# myDuino_v1_0.net
KiCad netlist of a schematic drawn in EAGLE
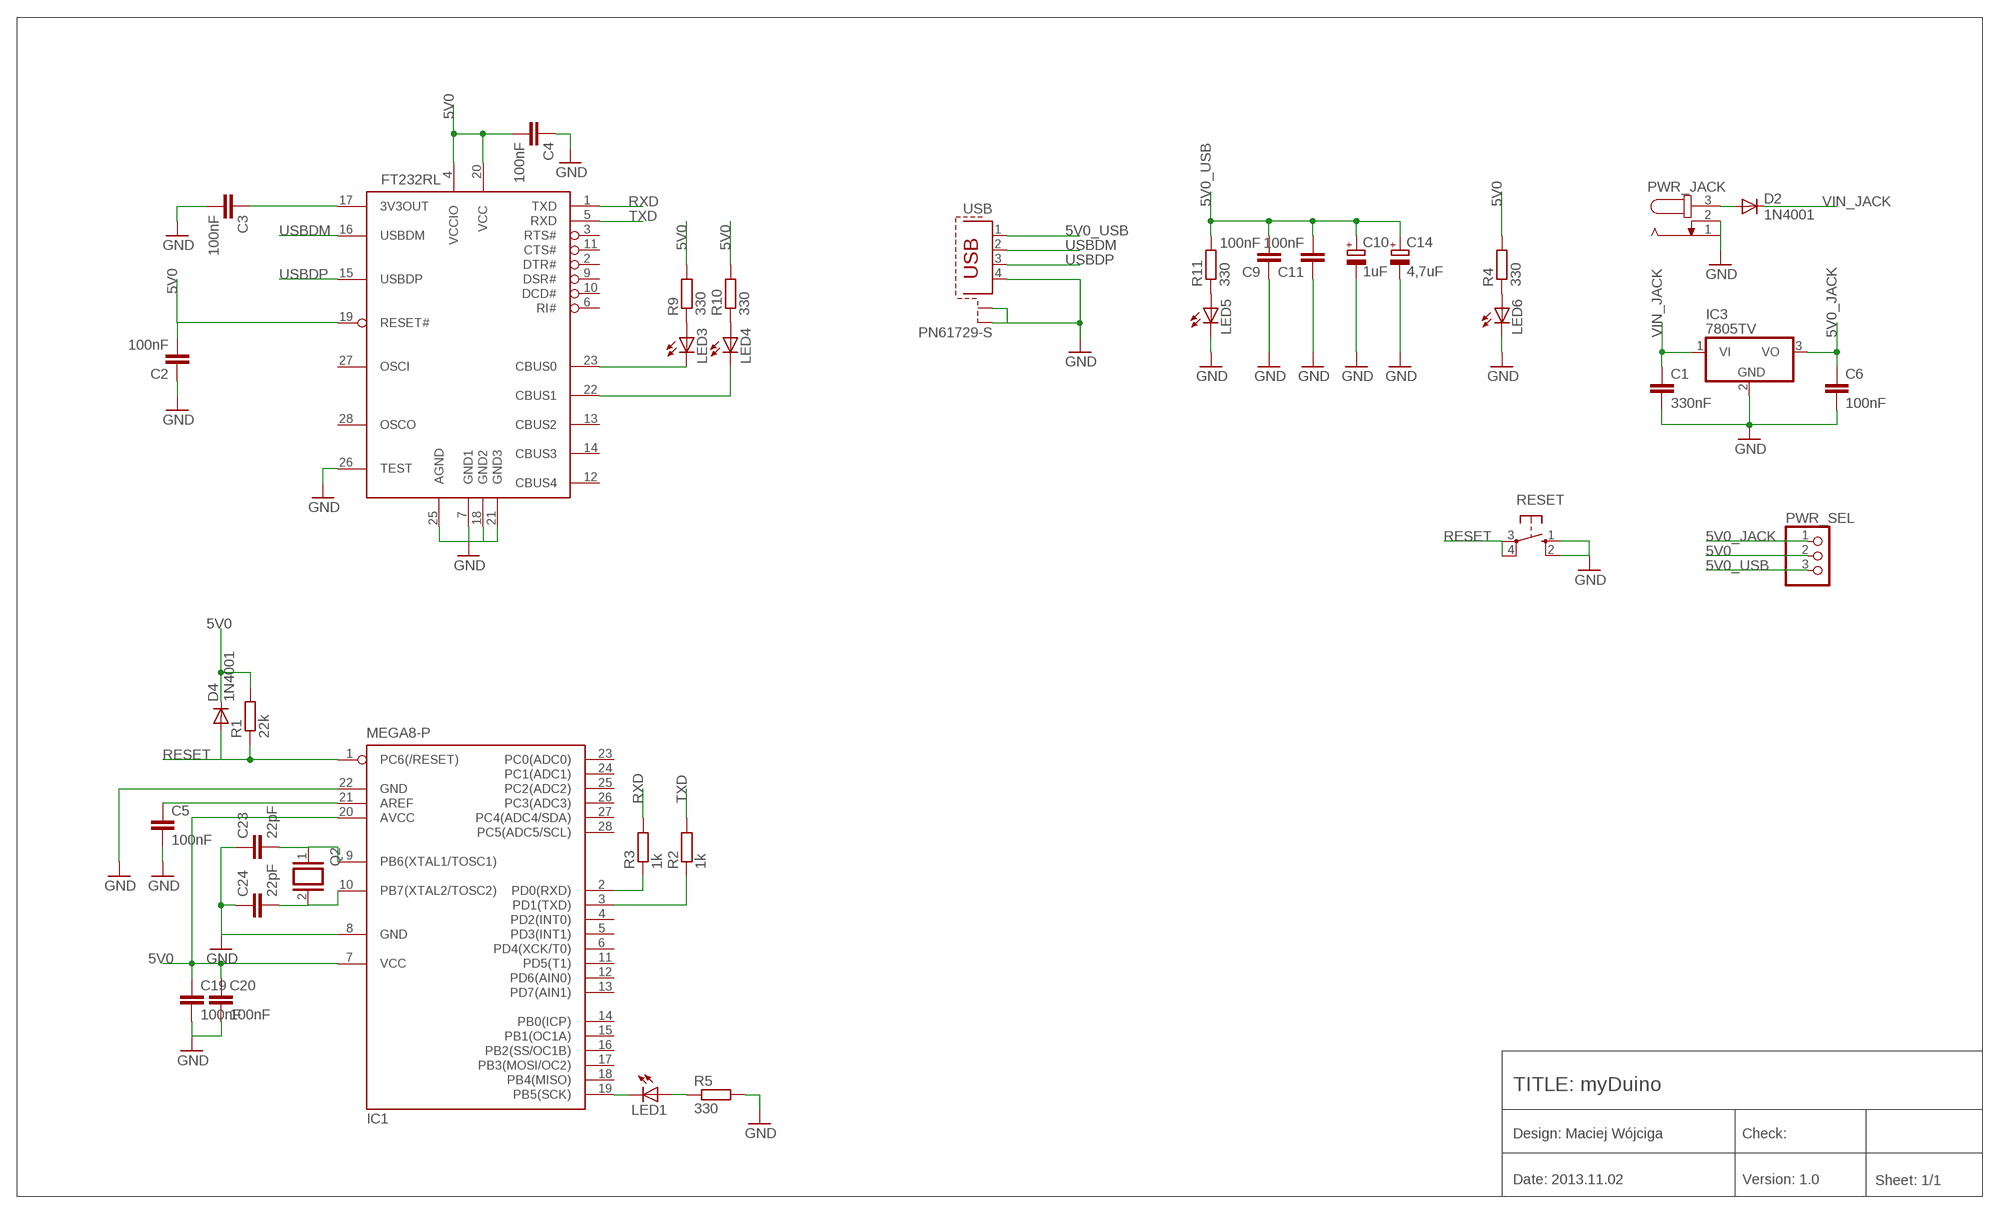
[diagram p0: schematic, sheet 1]

(export (version "E")
  (design (tool "Eeschema 10.0.6"))
  (components
    (comp (ref "C1")
      (value "330nF")
      (footprint "eagle-import:C025-025X050")
      (libsource (lib "eagle-import") (part "C-EU025-025X050"))
    )
    (comp (ref "C2")
      (value "100nF")
      (footprint "eagle-import:C025-025X050")
      (libsource (lib "eagle-import") (part "C-EU025-025X050"))
    )
    (comp (ref "C3")
      (value "100nF")
      (footprint "eagle-import:C025-025X050")
      (libsource (lib "eagle-import") (part "C-EU025-025X050"))
    )
    (comp (ref "C4")
      (value "100nF")
      (footprint "eagle-import:C025-025X050")
      (libsource (lib "eagle-import") (part "C-EU025-025X050"))
    )
    (comp (ref "C5")
      (value "100nF")
      (footprint "eagle-import:C025-025X050")
      (libsource (lib "eagle-import") (part "C-EU025-025X050"))
    )
    (comp (ref "C6")
      (value "100nF")
      (footprint "eagle-import:C025-025X050")
      (libsource (lib "eagle-import") (part "C-EU025-025X050"))
    )
    (comp (ref "C9")
      (value "100nF")
      (footprint "eagle-import:C025-025X050")
      (libsource (lib "eagle-import") (part "C-EU025-025X050"))
    )
    (comp (ref "C10")
      (value "1uF")
      (footprint "eagle-import:E2,5-5")
      (libsource (lib "eagle-import") (part "CPOL-EUE2.5-5"))
    )
    (comp (ref "C11")
      (value "100nF")
      (footprint "eagle-import:C025-025X050")
      (libsource (lib "eagle-import") (part "C-EU025-025X050"))
    )
    (comp (ref "C14")
      (value "4,7uF")
      (footprint "eagle-import:E2,5-5")
      (libsource (lib "eagle-import") (part "CPOL-EUE2.5-5"))
    )
    (comp (ref "C19")
      (value "100nF")
      (footprint "eagle-import:C025-025X050")
      (libsource (lib "eagle-import") (part "C-EU025-025X050"))
    )
    (comp (ref "C20")
      (value "100nF")
      (footprint "eagle-import:C025-025X050")
      (libsource (lib "eagle-import") (part "C-EU025-025X050"))
    )
    (comp (ref "C23")
      (value "22pF")
      (footprint "eagle-import:C025-025X050")
      (libsource (lib "eagle-import") (part "C-EU025-025X050"))
    )
    (comp (ref "C24")
      (value "22pF")
      (footprint "eagle-import:C025-025X050")
      (libsource (lib "eagle-import") (part "C-EU025-025X050"))
    )
    (comp (ref "D2")
      (value "1N4001")
      (footprint "eagle-import:DO41-10")
      (libsource (lib "eagle-import") (part "1N4004"))
    )
    (comp (ref "D4")
      (value "1N4001")
      (footprint "eagle-import:DO41-10")
      (libsource (lib "eagle-import") (part "1N4004"))
    )
    (comp (ref "FT232RL")
      (value "FT232RL")
      (footprint "eagle-import:SSOP28DB")
      (libsource (lib "eagle-import") (part "FT232RL"))
    )
    (comp (ref "IC1")
      (value "MEGA8-P")
      (footprint "eagle-import:DIL28-3")
      (libsource (lib "eagle-import") (part "MEGA8-P"))
    )
    (comp (ref "IC3")
      (value "7805TV")
      (footprint "eagle-import:TO220V")
      (libsource (lib "eagle-import") (part "78TV05"))
    )
    (comp (ref "LED1")
      (value "LED3MM")
      (footprint "eagle-import:LED3MM")
      (libsource (lib "eagle-import") (part "LED3MM"))
    )
    (comp (ref "LED3")
      (value "LED3MM")
      (footprint "eagle-import:LED3MM")
      (libsource (lib "eagle-import") (part "LED3MM"))
    )
    (comp (ref "LED4")
      (value "LED3MM")
      (footprint "eagle-import:LED3MM")
      (libsource (lib "eagle-import") (part "LED3MM"))
    )
    (comp (ref "LED5")
      (value "LED3MM")
      (footprint "eagle-import:LED3MM")
      (libsource (lib "eagle-import") (part "LED3MM"))
    )
    (comp (ref "LED6")
      (value "LED3MM")
      (footprint "eagle-import:LED3MM")
      (libsource (lib "eagle-import") (part "LED3MM"))
    )
    (comp (ref "PWR_JACK")
      (value "JACK-PLUG0")
      (footprint "eagle-import:SPC4077")
      (libsource (lib "eagle-import") (part "JACK-PLUG0"))
    )
    (comp (ref "PWR_SEL")
      (value "PINHD-1X3")
      (footprint "eagle-import:1X03")
      (libsource (lib "eagle-import") (part "PINHD-1X3"))
    )
    (comp (ref "Q2")
      (value "XTAL/S")
      (footprint "eagle-import:QS")
      (libsource (lib "eagle-import") (part "XTAL/S"))
    )
    (comp (ref "R1")
      (value "22k")
      (footprint "eagle-import:0207_10")
      (libsource (lib "eagle-import") (part "R-EU_0207/10"))
    )
    (comp (ref "R2")
      (value "1k")
      (footprint "eagle-import:0207_10")
      (libsource (lib "eagle-import") (part "R-EU_0207/10"))
    )
    (comp (ref "R3")
      (value "1k")
      (footprint "eagle-import:0207_10")
      (libsource (lib "eagle-import") (part "R-EU_0207/10"))
    )
    (comp (ref "R4")
      (value "330")
      (footprint "eagle-import:0207_10")
      (libsource (lib "eagle-import") (part "R-EU_0207/10"))
    )
    (comp (ref "R5")
      (value "330")
      (footprint "eagle-import:0207_10")
      (libsource (lib "eagle-import") (part "R-EU_0207/10"))
    )
    (comp (ref "R9")
      (value "330")
      (footprint "eagle-import:0207_10")
      (libsource (lib "eagle-import") (part "R-EU_0207/10"))
    )
    (comp (ref "R10")
      (value "330")
      (footprint "eagle-import:0207_10")
      (libsource (lib "eagle-import") (part "R-EU_0207/10"))
    )
    (comp (ref "R11")
      (value "330")
      (footprint "eagle-import:0207_10")
      (libsource (lib "eagle-import") (part "R-EU_0207/10"))
    )
    (comp (ref "RESET")
      (value "10-XX")
      (footprint "eagle-import:B3F-10XX")
      (fields (field (name "MPN") "B3F-1000"))
      (libsource (lib "eagle-import") (part "10-XX"))
    )
    (comp (ref "USB")
      (value "PN61729-S")
      (footprint "eagle-import:PN61729-S")
      (fields (field (name "OC_FARNELL") "unknown") (field (name "OC_NEWARK") "unknown"))
      (libsource (lib "eagle-import") (part "PN61729-S"))
    )
  )
  (nets
    (net (code "1") (name "/5V0") (class "Default")
      (node (ref "C19") (pin "1") (pinfunction "1_1") (pintype "passive"))
      (node (ref "C2") (pin "2") (pinfunction "2_2") (pintype "passive"))
      (node (ref "C20") (pin "1") (pinfunction "1_1") (pintype "passive"))
      (node (ref "C4") (pin "2") (pinfunction "2_2") (pintype "passive"))
      (node (ref "D4") (pin "C") (pinfunction "C_C") (pintype "passive"))
      (node (ref "FT232RL") (pin "19") (pinfunction "RESET#_19") (pintype "input"))
      (node (ref "FT232RL") (pin "20") (pinfunction "VCC_20") (pintype "power_in"))
      (node (ref "FT232RL") (pin "4") (pinfunction "VCCIO_4") (pintype "power_in"))
      (node (ref "IC1") (pin "20") (pinfunction "AVCC_20") (pintype "power_in"))
      (node (ref "IC1") (pin "7") (pinfunction "VCC_7") (pintype "power_in"))
      (node (ref "PWR_SEL") (pin "2") (pinfunction "2_2") (pintype "passive"))
      (node (ref "R1") (pin "2") (pinfunction "2_2") (pintype "passive"))
      (node (ref "R10") (pin "2") (pinfunction "2_2") (pintype "passive"))
      (node (ref "R4") (pin "2") (pinfunction "2_2") (pintype "passive"))
      (node (ref "R9") (pin "2") (pinfunction "2_2") (pintype "passive"))
    )
    (net (code "2") (name "/5V0_JACK") (class "Default")
      (node (ref "C6") (pin "1") (pinfunction "1_1") (pintype "passive"))
      (node (ref "IC3") (pin "3") (pinfunction "VO_3") (pintype "passive"))
      (node (ref "PWR_SEL") (pin "1") (pinfunction "1_1") (pintype "passive"))
    )
    (net (code "3") (name "/5V0_USB") (class "Default")
      (node (ref "C10") (pin "+") (pinfunction "+_+") (pintype "passive"))
      (node (ref "C11") (pin "2") (pinfunction "2_2") (pintype "passive"))
      (node (ref "C14") (pin "+") (pinfunction "+_+") (pintype "passive"))
      (node (ref "C9") (pin "2") (pinfunction "2_2") (pintype "passive"))
      (node (ref "PWR_SEL") (pin "3") (pinfunction "3_3") (pintype "passive"))
      (node (ref "R11") (pin "2") (pinfunction "2_2") (pintype "passive"))
      (node (ref "USB") (pin "1") (pinfunction "1_1") (pintype "passive"))
    )
    (net (code "4") (name "/RESET") (class "Default")
      (node (ref "D4") (pin "A") (pinfunction "A_A") (pintype "passive"))
      (node (ref "IC1") (pin "1") (pinfunction "PC6(/RESET)_1") (pintype "bidirectional"))
      (node (ref "R1") (pin "1") (pinfunction "1_1") (pintype "passive"))
      (node (ref "RESET") (pin "3") (pinfunction "P_3") (pintype "passive"))
      (node (ref "RESET") (pin "4") (pinfunction "P1_4") (pintype "passive"))
    )
    (net (code "5") (name "/RXD") (class "Default")
      (node (ref "FT232RL") (pin "1") (pinfunction "TXD_1") (pintype "output"))
      (node (ref "R3") (pin "2") (pinfunction "2_2") (pintype "passive"))
    )
    (net (code "6") (name "/TXD") (class "Default")
      (node (ref "FT232RL") (pin "5") (pinfunction "RXD_5") (pintype "input"))
      (node (ref "R2") (pin "2") (pinfunction "2_2") (pintype "passive"))
    )
    (net (code "7") (name "/USBDM") (class "Default")
      (node (ref "FT232RL") (pin "16") (pinfunction "USBDM_16") (pintype "bidirectional"))
      (node (ref "USB") (pin "2") (pinfunction "2_2") (pintype "passive"))
    )
    (net (code "8") (name "/USBDP") (class "Default")
      (node (ref "FT232RL") (pin "15") (pinfunction "USBDP_15") (pintype "bidirectional"))
      (node (ref "USB") (pin "3") (pinfunction "3_3") (pintype "passive"))
    )
    (net (code "9") (name "/VIN_JACK") (class "Default")
      (node (ref "C1") (pin "1") (pinfunction "1_1") (pintype "passive"))
      (node (ref "D2") (pin "C") (pinfunction "C_C") (pintype "passive"))
      (node (ref "IC3") (pin "1") (pinfunction "VI_1") (pintype "input"))
    )
    (net (code "10") (name "GND") (class "Default")
      (node (ref "C1") (pin "2") (pinfunction "2_2") (pintype "passive"))
      (node (ref "C10") (pin "-") (pinfunction "-_-") (pintype "passive"))
      (node (ref "C11") (pin "1") (pinfunction "1_1") (pintype "passive"))
      (node (ref "C14") (pin "-") (pinfunction "-_-") (pintype "passive"))
      (node (ref "C19") (pin "2") (pinfunction "2_2") (pintype "passive"))
      (node (ref "C2") (pin "1") (pinfunction "1_1") (pintype "passive"))
      (node (ref "C20") (pin "2") (pinfunction "2_2") (pintype "passive"))
      (node (ref "C23") (pin "1") (pinfunction "1_1") (pintype "passive"))
      (node (ref "C24") (pin "1") (pinfunction "1_1") (pintype "passive"))
      (node (ref "C3") (pin "2") (pinfunction "2_2") (pintype "passive"))
      (node (ref "C4") (pin "1") (pinfunction "1_1") (pintype "passive"))
      (node (ref "C5") (pin "2") (pinfunction "2_2") (pintype "passive"))
      (node (ref "C6") (pin "2") (pinfunction "2_2") (pintype "passive"))
      (node (ref "C9") (pin "1") (pinfunction "1_1") (pintype "passive"))
      (node (ref "FT232RL") (pin "18") (pinfunction "GND2_18") (pintype "power_in"))
      (node (ref "FT232RL") (pin "21") (pinfunction "GND3_21") (pintype "power_in"))
      (node (ref "FT232RL") (pin "25") (pinfunction "AGND_25") (pintype "power_in"))
      (node (ref "FT232RL") (pin "26") (pinfunction "TEST_26") (pintype "input"))
      (node (ref "FT232RL") (pin "7") (pinfunction "GND1_7") (pintype "power_in"))
      (node (ref "IC1") (pin "22") (pinfunction "GND_22") (pintype "power_in"))
      (node (ref "IC1") (pin "8") (pinfunction "GND_8") (pintype "power_in"))
      (node (ref "IC3") (pin "2") (pinfunction "GND_2") (pintype "passive"))
      (node (ref "LED5") (pin "K") (pinfunction "C_K") (pintype "passive"))
      (node (ref "LED6") (pin "K") (pinfunction "C_K") (pintype "passive"))
      (node (ref "PWR_JACK") (pin "1") (pinfunction "1_1") (pintype "passive"))
      (node (ref "PWR_JACK") (pin "2") (pinfunction "2_2") (pintype "passive"))
      (node (ref "R5") (pin "2") (pinfunction "2_2") (pintype "passive"))
      (node (ref "RESET") (pin "1") (pinfunction "S_1") (pintype "passive"))
      (node (ref "RESET") (pin "2") (pinfunction "S1_2") (pintype "passive"))
      (node (ref "USB") (pin "4") (pinfunction "4_4") (pintype "passive"))
      (node (ref "USB") (pin "S1") (pinfunction "S1_S1") (pintype "passive"))
      (node (ref "USB") (pin "S2") (pinfunction "S2_S2") (pintype "passive"))
    )
    (net (code "11") (name "Net-(D2-PadA)") (class "Default")
      (node (ref "D2") (pin "A") (pinfunction "A_A") (pintype "passive"))
      (node (ref "PWR_JACK") (pin "3") (pinfunction "3_3") (pintype "passive"))
    )
    (net (code "12") (name "Net-(FT232RL-3V3OUT)") (class "Default")
      (node (ref "C3") (pin "1") (pinfunction "1_1") (pintype "passive"))
      (node (ref "FT232RL") (pin "17") (pinfunction "3V3OUT_17") (pintype "output"))
    )
    (net (code "13") (name "Net-(FT232RL-CBUS0)") (class "Default")
      (node (ref "FT232RL") (pin "23") (pinfunction "CBUS0_23") (pintype "bidirectional"))
      (node (ref "LED3") (pin "K") (pinfunction "C_K") (pintype "passive"))
    )
    (net (code "14") (name "Net-(FT232RL-CBUS1)") (class "Default")
      (node (ref "FT232RL") (pin "22") (pinfunction "CBUS1_22") (pintype "bidirectional"))
      (node (ref "LED4") (pin "K") (pinfunction "C_K") (pintype "passive"))
    )
    (net (code "15") (name "Net-(IC1-AREF)") (class "Default")
      (node (ref "C5") (pin "1") (pinfunction "1_1") (pintype "passive"))
      (node (ref "IC1") (pin "21") (pinfunction "AREF_21") (pintype "passive"))
    )
    (net (code "16") (name "Net-(IC1-PB5(SCK))") (class "Default")
      (node (ref "IC1") (pin "19") (pinfunction "PB5(SCK)_19") (pintype "bidirectional"))
      (node (ref "LED1") (pin "K") (pinfunction "C_K") (pintype "passive"))
    )
    (net (code "17") (name "Net-(IC1-PB6(XTAL1{slash}TOSC1))") (class "Default")
      (node (ref "C23") (pin "2") (pinfunction "2_2") (pintype "passive"))
      (node (ref "IC1") (pin "9") (pinfunction "PB6(XTAL1/TOSC1)_9") (pintype "bidirectional"))
      (node (ref "Q2") (pin "1") (pinfunction "1_1") (pintype "passive"))
    )
    (net (code "18") (name "Net-(IC1-PB7(XTAL2{slash}TOSC2))") (class "Default")
      (node (ref "C24") (pin "2") (pinfunction "2_2") (pintype "passive"))
      (node (ref "IC1") (pin "10") (pinfunction "PB7(XTAL2/TOSC2)_10") (pintype "bidirectional"))
      (node (ref "Q2") (pin "2") (pinfunction "2_2") (pintype "passive"))
    )
    (net (code "19") (name "Net-(IC1-PD0(RXD))") (class "Default")
      (node (ref "IC1") (pin "2") (pinfunction "PD0(RXD)_2") (pintype "bidirectional"))
      (node (ref "R3") (pin "1") (pinfunction "1_1") (pintype "passive"))
    )
    (net (code "20") (name "Net-(IC1-PD1(TXD))") (class "Default")
      (node (ref "IC1") (pin "3") (pinfunction "PD1(TXD)_3") (pintype "bidirectional"))
      (node (ref "R2") (pin "1") (pinfunction "1_1") (pintype "passive"))
    )
    (net (code "21") (name "Net-(LED1-PadA)") (class "Default")
      (node (ref "LED1") (pin "A") (pinfunction "A_A") (pintype "passive"))
      (node (ref "R5") (pin "1") (pinfunction "1_1") (pintype "passive"))
    )
    (net (code "22") (name "Net-(LED3-PadA)") (class "Default")
      (node (ref "LED3") (pin "A") (pinfunction "A_A") (pintype "passive"))
      (node (ref "R9") (pin "1") (pinfunction "1_1") (pintype "passive"))
    )
    (net (code "23") (name "Net-(LED4-PadA)") (class "Default")
      (node (ref "LED4") (pin "A") (pinfunction "A_A") (pintype "passive"))
      (node (ref "R10") (pin "1") (pinfunction "1_1") (pintype "passive"))
    )
    (net (code "24") (name "Net-(LED5-PadA)") (class "Default")
      (node (ref "LED5") (pin "A") (pinfunction "A_A") (pintype "passive"))
      (node (ref "R11") (pin "1") (pinfunction "1_1") (pintype "passive"))
    )
    (net (code "25") (name "Net-(LED6-PadA)") (class "Default")
      (node (ref "LED6") (pin "A") (pinfunction "A_A") (pintype "passive"))
      (node (ref "R4") (pin "1") (pinfunction "1_1") (pintype "passive"))
    )
    (net (code "26") (name "unconnected-(FT232RL-CBUS2-Pad13)") (class "Default")
      (node (ref "FT232RL") (pin "13") (pinfunction "CBUS2_13") (pintype "bidirectional"))
    )
    (net (code "27") (name "unconnected-(FT232RL-CBUS3-Pad14)") (class "Default")
      (node (ref "FT232RL") (pin "14") (pinfunction "CBUS3_14") (pintype "bidirectional"))
    )
    (net (code "28") (name "unconnected-(FT232RL-CBUS4-Pad12)") (class "Default")
      (node (ref "FT232RL") (pin "12") (pinfunction "CBUS4_12") (pintype "bidirectional"))
    )
    (net (code "29") (name "unconnected-(FT232RL-CTS#-Pad11)") (class "Default")
      (node (ref "FT232RL") (pin "11") (pinfunction "CTS#_11") (pintype "input"))
    )
    (net (code "30") (name "unconnected-(FT232RL-DCD#-Pad10)") (class "Default")
      (node (ref "FT232RL") (pin "10") (pinfunction "DCD#_10") (pintype "input"))
    )
    (net (code "31") (name "unconnected-(FT232RL-DSR#-Pad9)") (class "Default")
      (node (ref "FT232RL") (pin "9") (pinfunction "DSR#_9") (pintype "input"))
    )
    (net (code "32") (name "unconnected-(FT232RL-DTR#-Pad2)") (class "Default")
      (node (ref "FT232RL") (pin "2") (pinfunction "DTR#_2") (pintype "output"))
    )
    (net (code "33") (name "unconnected-(FT232RL-OSCI-Pad27)") (class "Default")
      (node (ref "FT232RL") (pin "27") (pinfunction "OSCI_27") (pintype "input"))
    )
    (net (code "34") (name "unconnected-(FT232RL-OSCO-Pad28)") (class "Default")
      (node (ref "FT232RL") (pin "28") (pinfunction "OSCO_28") (pintype "output"))
    )
    (net (code "35") (name "unconnected-(FT232RL-RI#-Pad6)") (class "Default")
      (node (ref "FT232RL") (pin "6") (pinfunction "RI#_6") (pintype "input"))
    )
    (net (code "36") (name "unconnected-(FT232RL-RTS#-Pad3)") (class "Default")
      (node (ref "FT232RL") (pin "3") (pinfunction "RTS#_3") (pintype "output"))
    )
    (net (code "37") (name "unconnected-(IC1-PB0(ICP)-Pad14)") (class "Default")
      (node (ref "IC1") (pin "14") (pinfunction "PB0(ICP)_14") (pintype "bidirectional"))
    )
    (net (code "38") (name "unconnected-(IC1-PB1(OC1A)-Pad15)") (class "Default")
      (node (ref "IC1") (pin "15") (pinfunction "PB1(OC1A)_15") (pintype "bidirectional"))
    )
    (net (code "39") (name "unconnected-(IC1-PB2(SS{slash}OC1B)-Pad16)") (class "Default")
      (node (ref "IC1") (pin "16") (pinfunction "PB2(SS/OC1B)_16") (pintype "bidirectional"))
    )
    (net (code "40") (name "unconnected-(IC1-PB3(MOSI{slash}OC2)-Pad17)") (class "Default")
      (node (ref "IC1") (pin "17") (pinfunction "PB3(MOSI/OC2)_17") (pintype "bidirectional"))
    )
    (net (code "41") (name "unconnected-(IC1-PB4(MISO)-Pad18)") (class "Default")
      (node (ref "IC1") (pin "18") (pinfunction "PB4(MISO)_18") (pintype "bidirectional"))
    )
    (net (code "42") (name "unconnected-(IC1-PC0(ADC0)-Pad23)") (class "Default")
      (node (ref "IC1") (pin "23") (pinfunction "PC0(ADC0)_23") (pintype "bidirectional"))
    )
    (net (code "43") (name "unconnected-(IC1-PC1(ADC1)-Pad24)") (class "Default")
      (node (ref "IC1") (pin "24") (pinfunction "PC1(ADC1)_24") (pintype "bidirectional"))
    )
    (net (code "44") (name "unconnected-(IC1-PC2(ADC2)-Pad25)") (class "Default")
      (node (ref "IC1") (pin "25") (pinfunction "PC2(ADC2)_25") (pintype "bidirectional"))
    )
    (net (code "45") (name "unconnected-(IC1-PC3(ADC3)-Pad26)") (class "Default")
      (node (ref "IC1") (pin "26") (pinfunction "PC3(ADC3)_26") (pintype "bidirectional"))
    )
    (net (code "46") (name "unconnected-(IC1-PC4(ADC4{slash}SDA)-Pad27)") (class "Default")
      (node (ref "IC1") (pin "27") (pinfunction "PC4(ADC4/SDA)_27") (pintype "bidirectional"))
    )
    (net (code "47") (name "unconnected-(IC1-PC5(ADC5{slash}SCL)-Pad28)") (class "Default")
      (node (ref "IC1") (pin "28") (pinfunction "PC5(ADC5/SCL)_28") (pintype "bidirectional"))
    )
    (net (code "48") (name "unconnected-(IC1-PD2(INT0)-Pad4)") (class "Default")
      (node (ref "IC1") (pin "4") (pinfunction "PD2(INT0)_4") (pintype "bidirectional"))
    )
    (net (code "49") (name "unconnected-(IC1-PD3(INT1)-Pad5)") (class "Default")
      (node (ref "IC1") (pin "5") (pinfunction "PD3(INT1)_5") (pintype "bidirectional"))
    )
    (net (code "50") (name "unconnected-(IC1-PD4(XCK{slash}T0)-Pad6)") (class "Default")
      (node (ref "IC1") (pin "6") (pinfunction "PD4(XCK/T0)_6") (pintype "bidirectional"))
    )
    (net (code "51") (name "unconnected-(IC1-PD5(T1)-Pad11)") (class "Default")
      (node (ref "IC1") (pin "11") (pinfunction "PD5(T1)_11") (pintype "bidirectional"))
    )
    (net (code "52") (name "unconnected-(IC1-PD6(AIN0)-Pad12)") (class "Default")
      (node (ref "IC1") (pin "12") (pinfunction "PD6(AIN0)_12") (pintype "bidirectional"))
    )
    (net (code "53") (name "unconnected-(IC1-PD7(AIN1)-Pad13)") (class "Default")
      (node (ref "IC1") (pin "13") (pinfunction "PD7(AIN1)_13") (pintype "bidirectional"))
    )
  )
)
